# pcm2704_CMoy.net
KiCad netlist of a schematic drawn in EAGLE
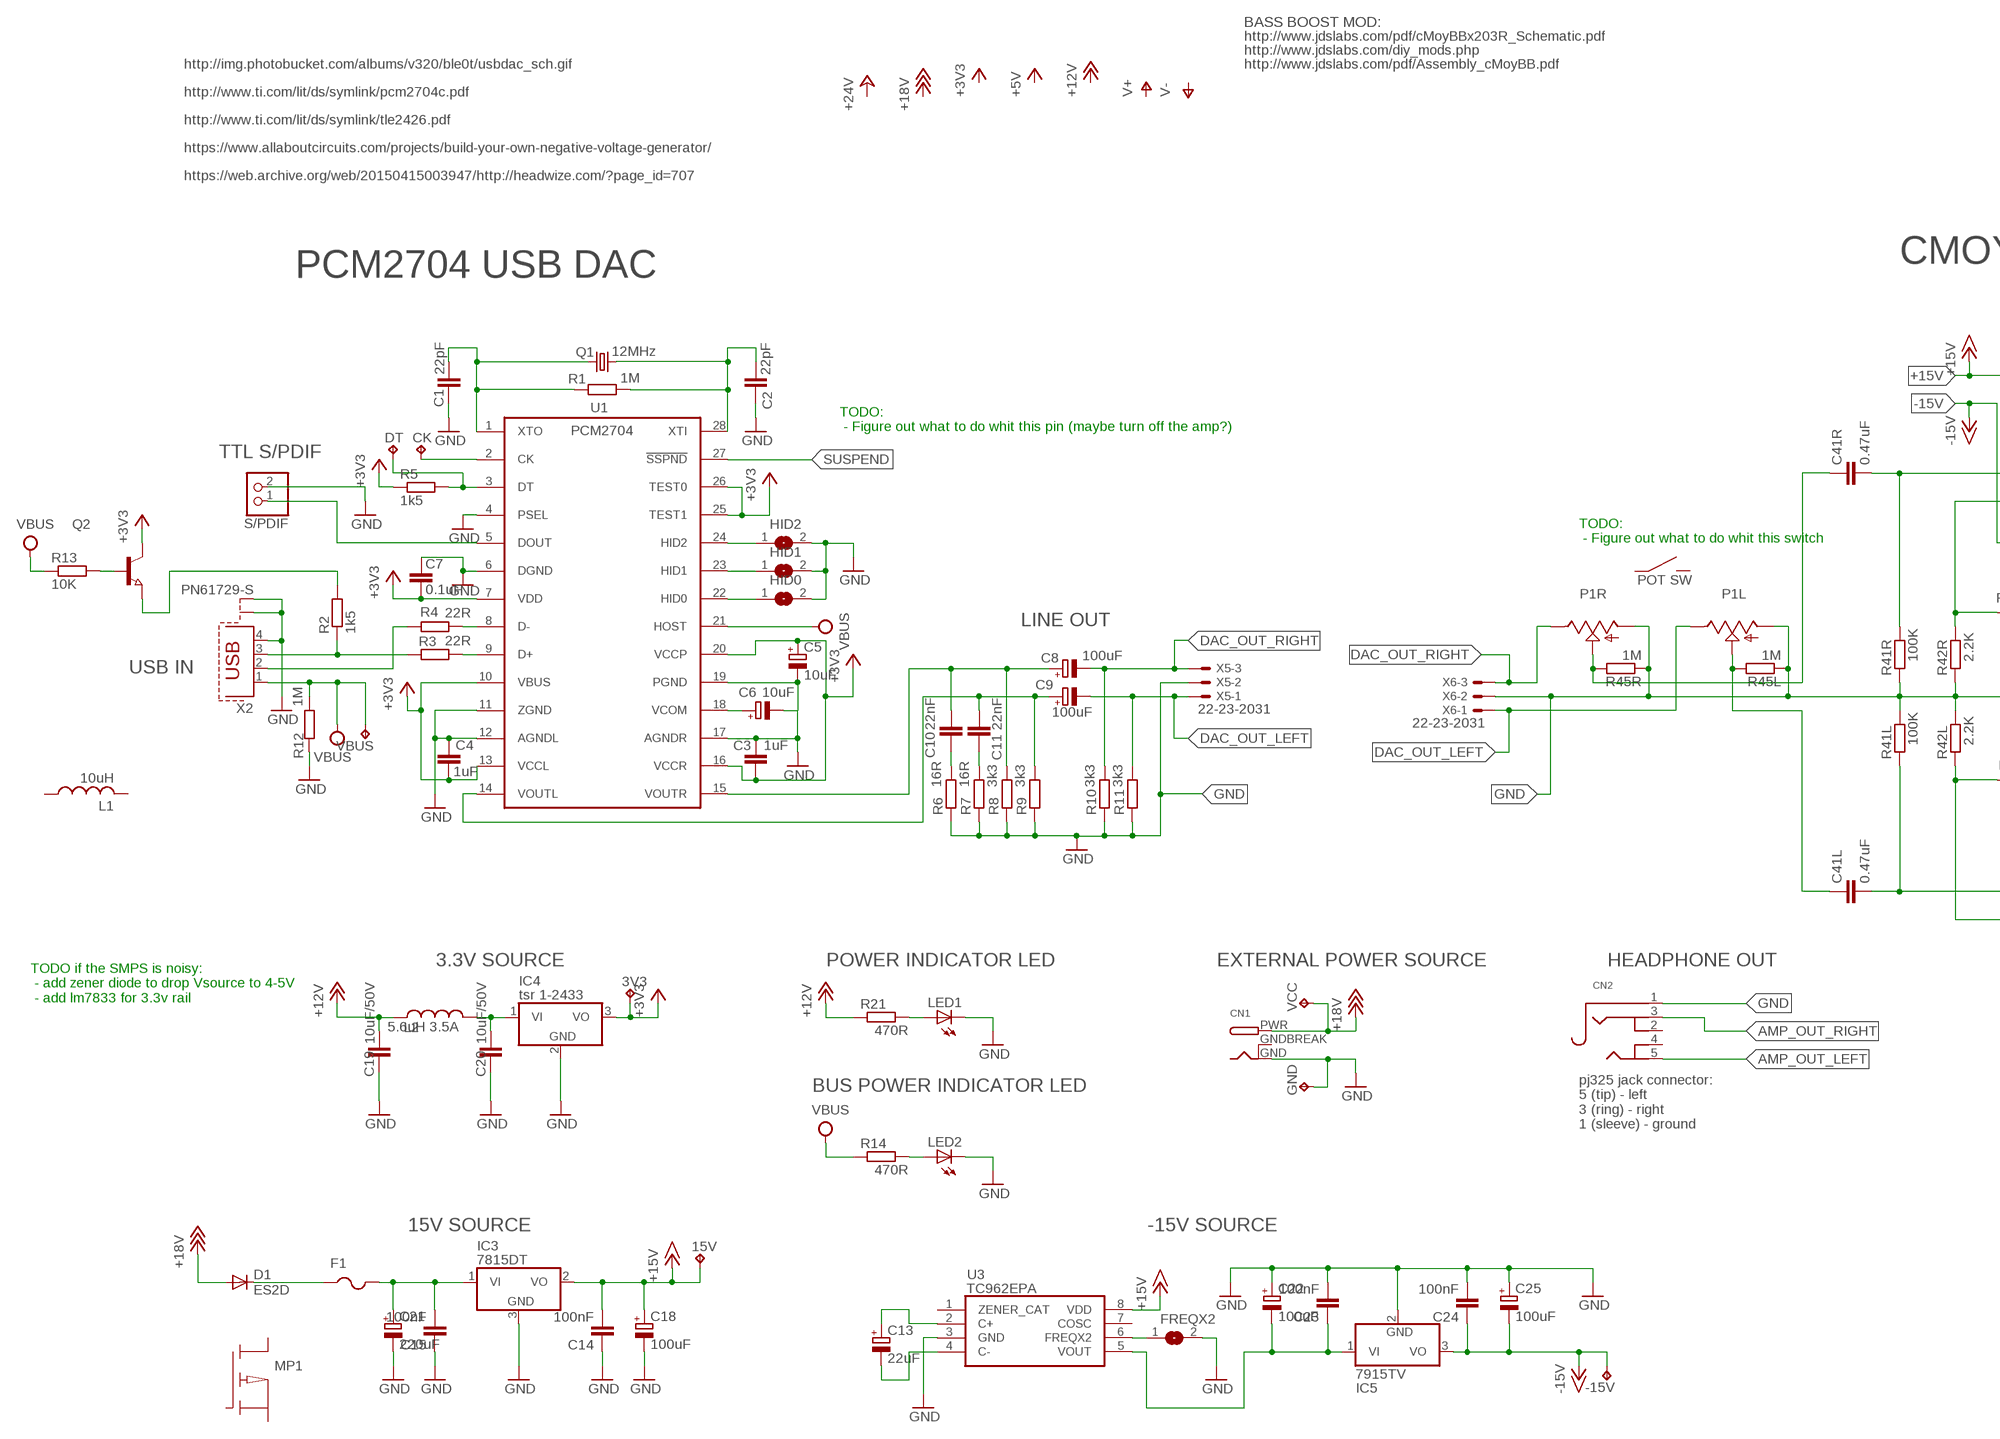
[diagram p0: schematic, sheet 1, part 1 of 2]
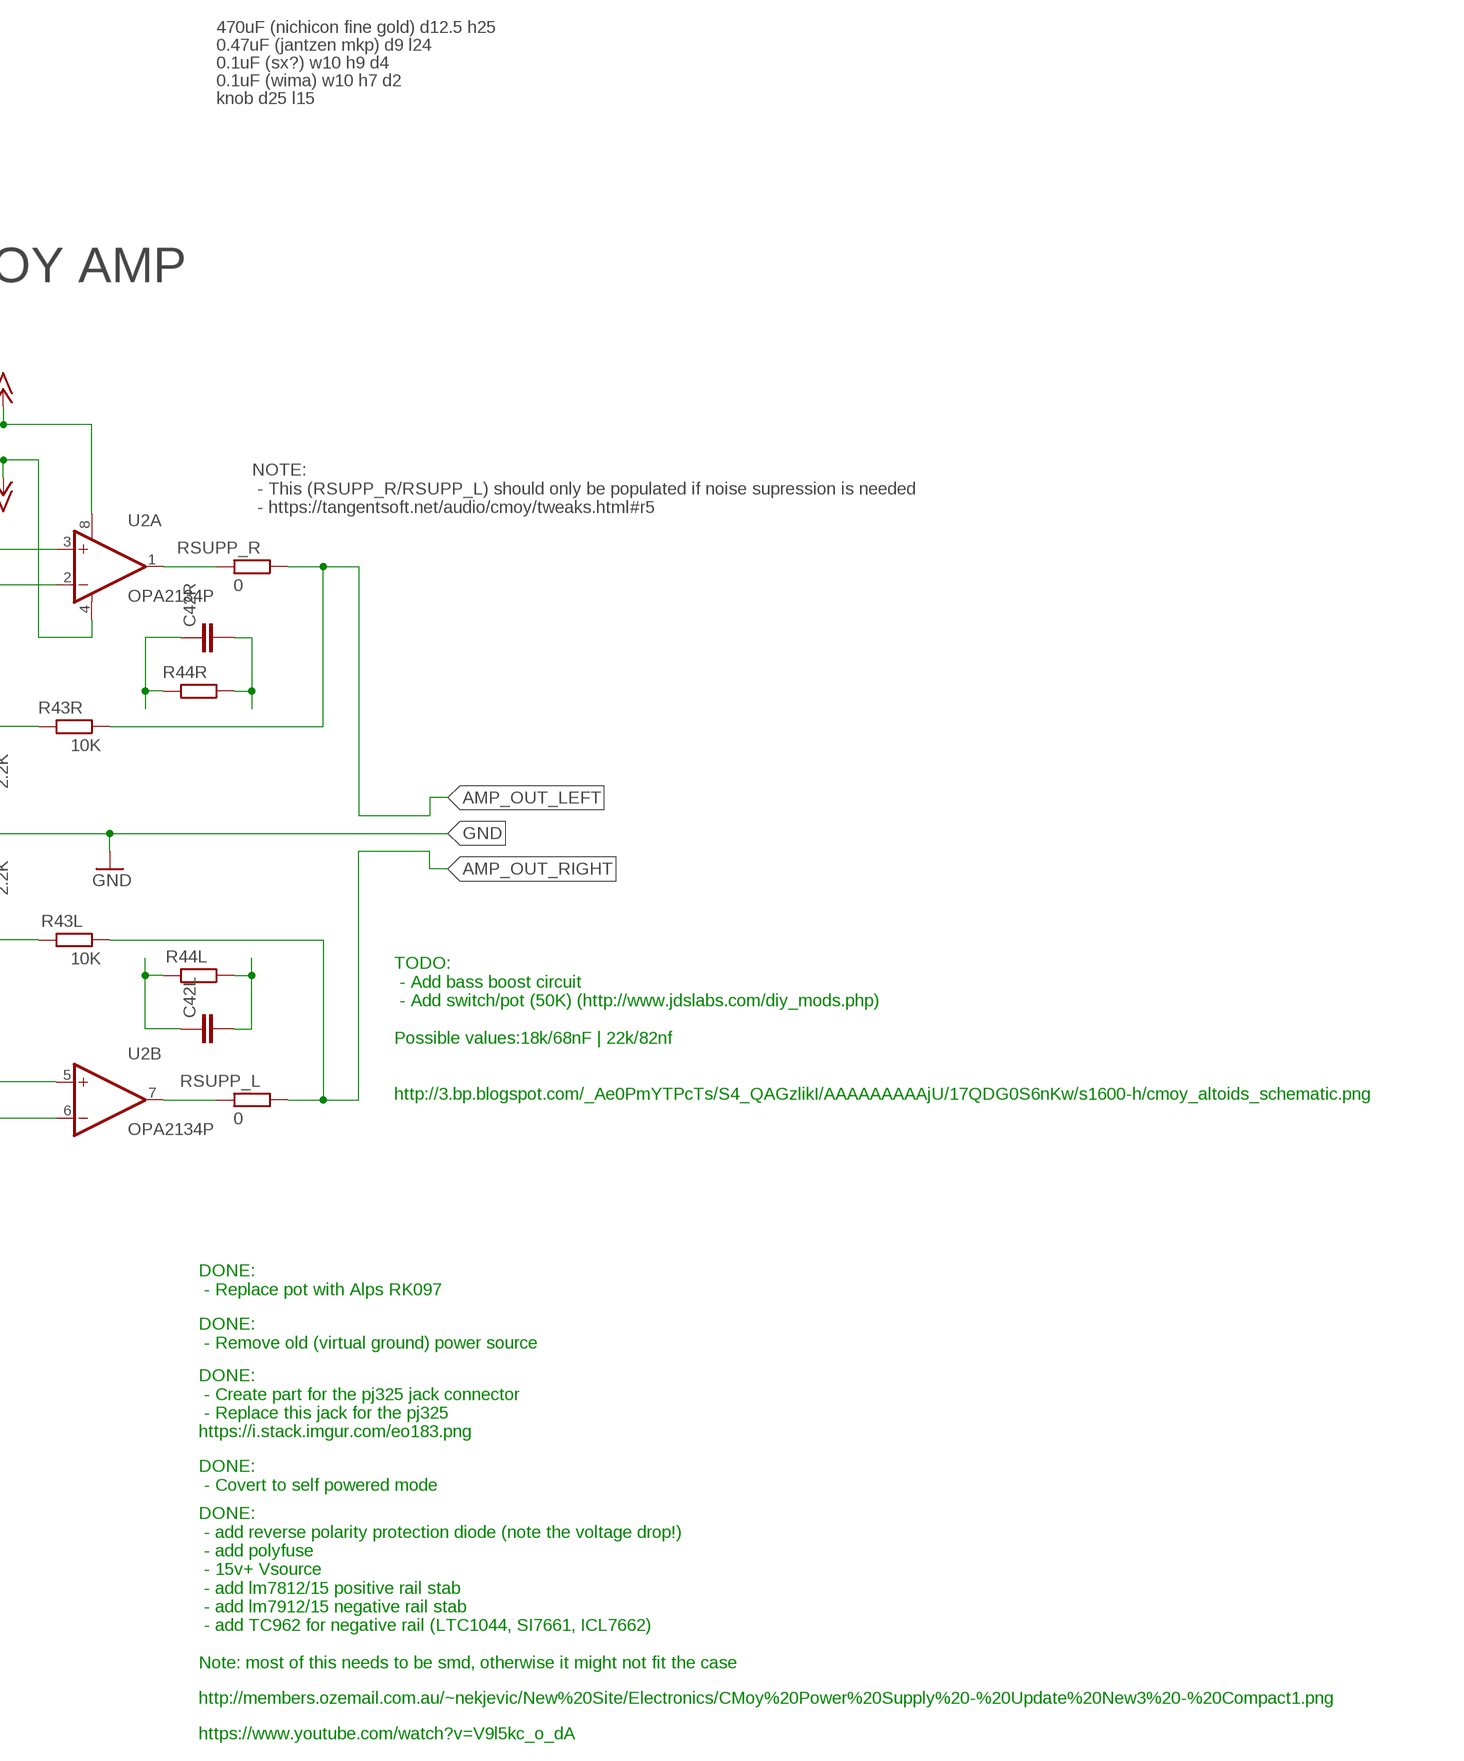
[diagram p1: schematic, sheet 1, part 2 of 2]

(export (version "E")
  (design (tool "Eeschema 10.0.6"))
  (components
    (comp (ref "-15V")
      (value "TPTP20R")
      (footprint "eagle-import:TP20R")
      (libsource (lib "eagle-import") (part "TPTP20R"))
    )
    (comp (ref "3V3")
      (value "TPTP20R")
      (footprint "eagle-import:TP20R")
      (libsource (lib "eagle-import") (part "TPTP20R"))
    )
    (comp (ref "15V")
      (value "TPTP20R")
      (footprint "eagle-import:TP20R")
      (libsource (lib "eagle-import") (part "TPTP20R"))
    )
    (comp (ref "C1")
      (value "22pF")
      (footprint "eagle-import:C0805")
      (libsource (lib "eagle-import") (part "C-EUC0805"))
    )
    (comp (ref "C2")
      (value "22pF")
      (footprint "eagle-import:C0805")
      (libsource (lib "eagle-import") (part "C-EUC0805"))
    )
    (comp (ref "C3")
      (value "1uF")
      (footprint "eagle-import:C0805")
      (libsource (lib "eagle-import") (part "C-EUC0805"))
    )
    (comp (ref "C4")
      (value "1uF")
      (footprint "eagle-import:C0805")
      (libsource (lib "eagle-import") (part "C-EUC0805"))
    )
    (comp (ref "C5")
      (value "10uF")
      (footprint "eagle-import:E2,5-7")
      (libsource (lib "eagle-import") (part "CPOL-EUE2.5-7"))
    )
    (comp (ref "C6")
      (value "10uF")
      (footprint "eagle-import:E2,5-7")
      (libsource (lib "eagle-import") (part "rcl_CPOL-EUE2.5-7"))
    )
    (comp (ref "C7")
      (value "0.1uF")
      (footprint "eagle-import:C0805")
      (libsource (lib "eagle-import") (part "C-EUC0805"))
    )
    (comp (ref "C8")
      (value "100uF")
      (footprint "eagle-import:E3,5-10")
      (libsource (lib "eagle-import") (part "rcl_CPOL-EUE3.5-10"))
    )
    (comp (ref "C9")
      (value "100uF")
      (footprint "eagle-import:E3,5-10")
      (libsource (lib "eagle-import") (part "rcl_CPOL-EUE3.5-10"))
    )
    (comp (ref "C10")
      (value "22nF")
      (footprint "eagle-import:C050-025X075")
      (libsource (lib "eagle-import") (part "C-EU050-025X075"))
    )
    (comp (ref "C11")
      (value "22nF")
      (footprint "eagle-import:C050-025X075")
      (libsource (lib "eagle-import") (part "C-EU050-025X075"))
    )
    (comp (ref "C13")
      (value "22uF")
      (footprint "eagle-import:E2,5-7")
      (libsource (lib "eagle-import") (part "rcl_CPOL-EUE2.5-7"))
    )
    (comp (ref "C14")
      (value "100nF")
      (footprint "eagle-import:C1206")
      (libsource (lib "eagle-import") (part "C-EUC1206"))
    )
    (comp (ref "C15")
      (value "100nF")
      (footprint "eagle-import:C1206")
      (libsource (lib "eagle-import") (part "C-EUC1206"))
    )
    (comp (ref "C18")
      (value "100uF")
      (footprint "eagle-import:E2,5-7")
      (libsource (lib "eagle-import") (part "rcl_CPOL-EUE2.5-7"))
    )
    (comp (ref "C19")
      (value "10uF/50V")
      (footprint "eagle-import:C1206")
      (libsource (lib "eagle-import") (part "C-EUC1206"))
    )
    (comp (ref "C20")
      (value "10uF/50V")
      (footprint "eagle-import:C1206")
      (libsource (lib "eagle-import") (part "C-EUC1206"))
    )
    (comp (ref "C21")
      (value "220uF")
      (footprint "eagle-import:E2,5-7")
      (libsource (lib "eagle-import") (part "rcl_CPOL-EUE2.5-7"))
    )
    (comp (ref "C22")
      (value "100uF")
      (footprint "eagle-import:E2,5-7")
      (libsource (lib "eagle-import") (part "rcl_CPOL-EUE2.5-7"))
    )
    (comp (ref "C23")
      (value "100nF")
      (footprint "eagle-import:C1206")
      (libsource (lib "eagle-import") (part "C-EUC1206"))
    )
    (comp (ref "C24")
      (value "100nF")
      (footprint "eagle-import:C1206")
      (libsource (lib "eagle-import") (part "C-EUC1206"))
    )
    (comp (ref "C25")
      (value "100uF")
      (footprint "eagle-import:E2,5-7")
      (libsource (lib "eagle-import") (part "rcl_CPOL-EUE2.5-7"))
    )
    (comp (ref "C41L")
      (value "0.47uF")
      (footprint "eagle-import:C27.5B11")
      (libsource (lib "eagle-import") (part "C27/11"))
    )
    (comp (ref "C41R")
      (value "0.47uF")
      (footprint "eagle-import:C27.5B11")
      (libsource (lib "eagle-import") (part "C27/11"))
    )
    (comp (ref "C42L")
      (value "C7.5/4")
      (footprint "eagle-import:C7.5B4")
      (libsource (lib "eagle-import") (part "C7.5/4"))
    )
    (comp (ref "C42R")
      (value "C7.5/4")
      (footprint "eagle-import:C7.5B4")
      (libsource (lib "eagle-import") (part "C7.5/4"))
    )
    (comp (ref "CK")
      (value "TPTP20R")
      (footprint "eagle-import:TP20R")
      (libsource (lib "eagle-import") (part "TPTP20R"))
    )
    (comp (ref "CN1")
      (value "DCBARRELPTH")
      (footprint "eagle-import:DCJACK_2MM_PTH")
      (libsource (lib "eagle-import") (part "DCBARRELPTH"))
    )
    (comp (ref "CN2")
      (value "AUDIO_3.5MMJACKPTH")
      (footprint "eagle-import:4UCONN_05550")
      (libsource (lib "eagle-import") (part "AUDIO_3.5MMJACKPTH"))
    )
    (comp (ref "D1")
      (value "ES2D")
      (footprint "eagle-import:SMB")
      (libsource (lib "eagle-import") (part "ES2D"))
    )
    (comp (ref "DT")
      (value "TPTP20R")
      (footprint "eagle-import:TP20R")
      (libsource (lib "eagle-import") (part "TPTP20R"))
    )
    (comp (ref "F1")
      (value "PTCFUSE-1812")
      (footprint "eagle-import:1812")
      (libsource (lib "eagle-import") (part "PTCFUSE-1812"))
    )
    (comp (ref "FREQX2")
      (value "SJ")
      (footprint "eagle-import:SJ")
      (libsource (lib "eagle-import") (part "SJ"))
    )
    (comp (ref "GND")
      (value "TPTP20R")
      (footprint "eagle-import:TP20R")
      (libsource (lib "eagle-import") (part "TPTP20R"))
    )
    (comp (ref "HID0")
      (value "SJ")
      (footprint "eagle-import:SJ")
      (libsource (lib "eagle-import") (part "SJ"))
    )
    (comp (ref "HID1")
      (value "SJ")
      (footprint "eagle-import:SJ")
      (libsource (lib "eagle-import") (part "SJ"))
    )
    (comp (ref "HID2")
      (value "SJ")
      (footprint "eagle-import:SJ")
      (libsource (lib "eagle-import") (part "SJ"))
    )
    (comp (ref "IC3")
      (value "7815DT")
      (footprint "eagle-import:TO252")
      (libsource (lib "eagle-import") (part "78DT15"))
    )
    (comp (ref "IC4")
      (value "tsr 1-2433")
      (footprint "eagle-import:TO220V")
      (libsource (lib "eagle-import") (part "78TV05"))
    )
    (comp (ref "IC5")
      (value "7915TV")
      (footprint "eagle-import:TO220V")
      (libsource (lib "eagle-import") (part "78TV15"))
    )
    (comp (ref "L1")
      (value "10uH")
      (footprint "eagle-import:L1812")
      (libsource (lib "eagle-import") (part "L-USL1812"))
    )
    (comp (ref "L2")
      (value "5.6uH 3.5A")
      (footprint "eagle-import:L1812")
      (libsource (lib "eagle-import") (part "L-USL1812"))
    )
    (comp (ref "LED1")
      (value "LED3MM")
      (footprint "eagle-import:LED3MM")
      (libsource (lib "eagle-import") (part "LED3MM"))
    )
    (comp (ref "LED2")
      (value "LED3MM")
      (footprint "eagle-import:LED3MM")
      (libsource (lib "eagle-import") (part "LED3MM"))
    )
    (comp (ref "MP1")
      (value "PMOS")
      (footprint "eagle-import:SOT23")
      (libsource (lib "eagle-import") (part "PMOS"))
    )
    (comp (ref "P1")
      (value "ALPS_RK0971221Z0N")
      (footprint "eagle-import:ALPS_RK0971221Z0X")
      (libsource (lib "eagle-import") (part "ALPS_RK0971221Z0N"))
    )
    (comp (ref "Q1")
      (value "12MHz")
      (footprint "eagle-import:HC49_S")
      (libsource (lib "eagle-import") (part "CRYSTALHC49S"))
    )
    (comp (ref "Q2")
      (value "NPN-TRANSISTOR_SOT23")
      (footprint "eagle-import:SOT23")
      (libsource (lib "eagle-import") (part "NPN-TRANSISTOR_SOT23"))
    )
    (comp (ref "R1")
      (value "1M")
      (footprint "eagle-import:M0805")
      (libsource (lib "eagle-import") (part "R-EU_M0805"))
    )
    (comp (ref "R2")
      (value "1k5")
      (footprint "eagle-import:R0805")
      (libsource (lib "eagle-import") (part "R-EU_R0805"))
    )
    (comp (ref "R3")
      (value "22R")
      (footprint "eagle-import:R0805")
      (libsource (lib "eagle-import") (part "R-EU_R0805"))
    )
    (comp (ref "R4")
      (value "22R")
      (footprint "eagle-import:R0805")
      (libsource (lib "eagle-import") (part "R-EU_R0805"))
    )
    (comp (ref "R5")
      (value "1k5")
      (footprint "eagle-import:R0805")
      (libsource (lib "eagle-import") (part "R-EU_R0805"))
    )
    (comp (ref "R6")
      (value "16R")
      (footprint "eagle-import:0204_7")
      (libsource (lib "eagle-import") (part "R-EU_0204/7"))
    )
    (comp (ref "R7")
      (value "16R")
      (footprint "eagle-import:0204_7")
      (libsource (lib "eagle-import") (part "R-EU_0204/7"))
    )
    (comp (ref "R8")
      (value "3k3")
      (footprint "eagle-import:0204_7")
      (libsource (lib "eagle-import") (part "R-EU_0204/7"))
    )
    (comp (ref "R9")
      (value "3k3")
      (footprint "eagle-import:0204_7")
      (libsource (lib "eagle-import") (part "R-EU_0204/7"))
    )
    (comp (ref "R10")
      (value "3k3")
      (footprint "eagle-import:0204_7")
      (libsource (lib "eagle-import") (part "R-EU_0204/7"))
    )
    (comp (ref "R11")
      (value "3k3")
      (footprint "eagle-import:0204_7")
      (libsource (lib "eagle-import") (part "R-EU_0204/7"))
    )
    (comp (ref "R12")
      (value "1M")
      (footprint "eagle-import:M0805")
      (libsource (lib "eagle-import") (part "R-EU_M0805"))
    )
    (comp (ref "R13")
      (value "10K")
      (footprint "eagle-import:R0805")
      (libsource (lib "eagle-import") (part "R-EU_R0805"))
    )
    (comp (ref "R14")
      (value "470R")
      (footprint "eagle-import:0204_7")
      (libsource (lib "eagle-import") (part "R-EU_0204/7"))
    )
    (comp (ref "R21")
      (value "470R")
      (footprint "eagle-import:0204_7")
      (libsource (lib "eagle-import") (part "R-EU_0204/7"))
    )
    (comp (ref "R41L")
      (value "100K")
      (footprint "eagle-import:0204_7")
      (libsource (lib "eagle-import") (part "R-EU_0204/7"))
    )
    (comp (ref "R41R")
      (value "100K")
      (footprint "eagle-import:0204_7")
      (libsource (lib "eagle-import") (part "R-EU_0204/7"))
    )
    (comp (ref "R42L")
      (value "2.2K")
      (footprint "eagle-import:0204_7")
      (libsource (lib "eagle-import") (part "R-EU_0204/7"))
    )
    (comp (ref "R42R")
      (value "2.2K")
      (footprint "eagle-import:0204_7")
      (libsource (lib "eagle-import") (part "R-EU_0204/7"))
    )
    (comp (ref "R43L")
      (value "10K")
      (footprint "eagle-import:0204_7")
      (libsource (lib "eagle-import") (part "R-EU_0204/7"))
    )
    (comp (ref "R43R")
      (value "10K")
      (footprint "eagle-import:0204_7")
      (libsource (lib "eagle-import") (part "R-EU_0204/7"))
    )
    (comp (ref "R44L")
      (value "R-EU_0204/7")
      (footprint "eagle-import:0204_7")
      (libsource (lib "eagle-import") (part "R-EU_0204/7"))
    )
    (comp (ref "R44R")
      (value "R-EU_0204/7")
      (footprint "eagle-import:0204_7")
      (libsource (lib "eagle-import") (part "R-EU_0204/7"))
    )
    (comp (ref "R45L")
      (value "1M")
      (footprint "eagle-import:0204_7")
      (libsource (lib "eagle-import") (part "R-EU_0204/7"))
    )
    (comp (ref "R45R")
      (value "1M")
      (footprint "eagle-import:0204_7")
      (libsource (lib "eagle-import") (part "R-EU_0204/7"))
    )
    (comp (ref "RSUPP_L")
      (value "0")
      (footprint "eagle-import:0204_7")
      (libsource (lib "eagle-import") (part "R-EU_0204/7"))
    )
    (comp (ref "RSUPP_R")
      (value "0")
      (footprint "eagle-import:0204_7")
      (libsource (lib "eagle-import") (part "R-EU_0204/7"))
    )
    (comp (ref "S/PDIF")
      (value "PINHD-1X2")
      (footprint "eagle-import:1X02")
      (libsource (lib "eagle-import") (part "PINHD-1X2"))
    )
    (comp (ref "U1")
      (value "PCM2704")
      (footprint "eagle-import:SSOP28DB")
      (libsource (lib "eagle-import") (part "PCM2704"))
    )
    (comp (ref "U2")
      (value "OPA2134P")
      (footprint "eagle-import:DIL08")
      (fields (field (name "MF") "TEXAS INSTRUMENTS") (field (name "MPN") "OPA2134PA"))
      (libsource (lib "eagle-import") (part "OPA2134P"))
    )
    (comp (ref "U3")
      (value "TC962EPA")
      (footprint "eagle-import:PDIP8_300MC")
      (libsource (lib "eagle-import") (part "TC962EPA"))
    )
    (comp (ref "VBUS")
      (value "TPTP20R")
      (footprint "eagle-import:TP20R")
      (libsource (lib "eagle-import") (part "TPTP20R"))
    )
    (comp (ref "VCC")
      (value "TPTP20R")
      (footprint "eagle-import:TP20R")
      (libsource (lib "eagle-import") (part "TPTP20R"))
    )
    (comp (ref "X2")
      (value "PN61729-S")
      (footprint "eagle-import:PN61729-S")
      (libsource (lib "eagle-import") (part "PN61729-S"))
    )
    (comp (ref "X5")
      (value "22-23-2031")
      (footprint "eagle-import:22-23-2031")
      (fields (field (name "MF") "MOLEX"))
      (libsource (lib "eagle-import") (part "22-23-2031"))
    )
    (comp (ref "X6")
      (value "22-23-2031")
      (footprint "eagle-import:22-23-2031")
      (fields (field (name "MF") "MOLEX"))
      (libsource (lib "eagle-import") (part "22-23-2031"))
    )
  )
  (nets
    (net (code "1") (name "+3V3") (class "Default")
      (node (ref "3V3") (pin "TP") (pinfunction "TP_TP") (pintype "input"))
      (node (ref "C3") (pin "1") (pinfunction "1_1") (pintype "passive"))
      (node (ref "C4") (pin "2") (pinfunction "2_2") (pintype "passive"))
      (node (ref "C5") (pin "+") (pinfunction "+_+") (pintype "passive"))
      (node (ref "C7") (pin "2") (pinfunction "2_2") (pintype "passive"))
      (node (ref "IC4") (pin "3") (pinfunction "VO_3") (pintype "passive"))
      (node (ref "Q2") (pin "3") (pinfunction "C_3") (pintype "passive"))
      (node (ref "R5") (pin "1") (pinfunction "1_1") (pintype "passive"))
      (node (ref "U1") (pin "10") (pinfunction "VBUS_10") (pintype "power_in"))
      (node (ref "U1") (pin "13") (pinfunction "VCCL_13") (pintype "power_in"))
      (node (ref "U1") (pin "16") (pinfunction "VCCR_16") (pintype "power_in"))
      (node (ref "U1") (pin "20") (pinfunction "VCCP_20") (pintype "power_in"))
      (node (ref "U1") (pin "25") (pinfunction "TEST1_25") (pintype "input"))
      (node (ref "U1") (pin "26") (pinfunction "TEST0_26") (pintype "input"))
      (node (ref "U1") (pin "7") (pinfunction "VDD_7") (pintype "power_in"))
    )
    (net (code "3") (name "+12V") (class "Default")
      (node (ref "C19") (pin "2") (pinfunction "2_2") (pintype "passive"))
      (node (ref "L2") (pin "1") (pinfunction "1_1") (pintype "passive"))
      (node (ref "R21") (pin "1") (pinfunction "1_1") (pintype "passive"))
    )
    (net (code "4") (name "+15V") (class "Default")
      (node (ref "15V") (pin "TP") (pinfunction "TP_TP") (pintype "input"))
      (node (ref "C14") (pin "2") (pinfunction "2_2") (pintype "passive"))
      (node (ref "C18") (pin "+") (pinfunction "+_+") (pintype "passive"))
      (node (ref "IC3") (pin "2") (pinfunction "VO_2") (pintype "passive"))
      (node (ref "U2") (pin "8") (pinfunction "V+_8") (pintype "power_in"))
      (node (ref "U3") (pin "8") (pinfunction "VDD_8") (pintype "passive"))
    )
    (net (code "5") (name "+18V") (class "Default")
      (node (ref "CN1") (pin "PWR") (pinfunction "PWR_PWR") (pintype "power_in"))
      (node (ref "D1") (pin "A") (pinfunction "A_A") (pintype "passive"))
      (node (ref "VCC") (pin "TP") (pinfunction "TP_TP") (pintype "input"))
    )
    (net (code "7") (name "-15V") (class "Default")
      (node (ref "-15V") (pin "TP") (pinfunction "TP_TP") (pintype "input"))
      (node (ref "C24") (pin "1") (pinfunction "1_1") (pintype "passive"))
      (node (ref "C25") (pin "-") (pinfunction "-_-") (pintype "passive"))
      (node (ref "IC5") (pin "3") (pinfunction "VO_3") (pintype "passive"))
      (node (ref "U2") (pin "4") (pinfunction "V-_4") (pintype "power_in"))
    )
    (net (code "8") (name "/GNDBREAK") (class "Default")
      (node (ref "CN1") (pin "GNDBREAK") (pinfunction "GNDBREAK_GNDBREAK") (pintype "power_in"))
    )
    (net (code "9") (name "/S1") (class "Default")
      (node (ref "P1") (pin "S1") (pinfunction "S1_S1") (pintype "power_in"))
    )
    (net (code "10") (name "/S2") (class "Default")
      (node (ref "P1") (pin "S2") (pinfunction "S2_S2") (pintype "power_in"))
    )
    (net (code "11") (name "AMP_OUT_LEFT") (class "Default")
      (node (ref "CN2") (pin "5") (pinfunction "P$5_5") (pintype "bidirectional"))
      (node (ref "R43R") (pin "1") (pinfunction "1_1") (pintype "passive"))
      (node (ref "RSUPP_R") (pin "1") (pinfunction "1_1") (pintype "passive"))
    )
    (net (code "12") (name "AMP_OUT_RIGHT") (class "Default")
      (node (ref "CN2") (pin "3") (pinfunction "P$2_3") (pintype "bidirectional"))
      (node (ref "R43L") (pin "1") (pinfunction "1_1") (pintype "passive"))
      (node (ref "RSUPP_L") (pin "1") (pinfunction "1_1") (pintype "passive"))
    )
    (net (code "13") (name "DAC_OUT_LEFT") (class "Default")
      (node (ref "C9") (pin "-") (pinfunction "-_-") (pintype "passive"))
      (node (ref "P1") (pin "I1") (pinfunction "3_I1") (pintype "passive"))
      (node (ref "R11") (pin "2") (pinfunction "2_2") (pintype "passive"))
      (node (ref "X5") (pin "1") (pinfunction "S_1") (pintype "passive"))
      (node (ref "X6") (pin "1") (pinfunction "S_1") (pintype "passive"))
    )
    (net (code "14") (name "DAC_OUT_RIGHT") (class "Default")
      (node (ref "C8") (pin "-") (pinfunction "-_-") (pintype "passive"))
      (node (ref "P1") (pin "I2") (pinfunction "3_I2") (pintype "passive"))
      (node (ref "R10") (pin "2") (pinfunction "2_2") (pintype "passive"))
      (node (ref "X5") (pin "3") (pinfunction "S_3") (pintype "passive"))
      (node (ref "X6") (pin "3") (pinfunction "S_3") (pintype "passive"))
    )
    (net (code "15") (name "GND") (class "Default")
      (node (ref "C1") (pin "2") (pinfunction "2_2") (pintype "passive"))
      (node (ref "C14") (pin "1") (pinfunction "1_1") (pintype "passive"))
      (node (ref "C15") (pin "1") (pinfunction "1_1") (pintype "passive"))
      (node (ref "C18") (pin "-") (pinfunction "-_-") (pintype "passive"))
      (node (ref "C19") (pin "1") (pinfunction "1_1") (pintype "passive"))
      (node (ref "C2") (pin "2") (pinfunction "2_2") (pintype "passive"))
      (node (ref "C20") (pin "1") (pinfunction "1_1") (pintype "passive"))
      (node (ref "C21") (pin "-") (pinfunction "-_-") (pintype "passive"))
      (node (ref "C22") (pin "+") (pinfunction "+_+") (pintype "passive"))
      (node (ref "C23") (pin "2") (pinfunction "2_2") (pintype "passive"))
      (node (ref "C24") (pin "2") (pinfunction "2_2") (pintype "passive"))
      (node (ref "C25") (pin "+") (pinfunction "+_+") (pintype "passive"))
      (node (ref "C3") (pin "2") (pinfunction "2_2") (pintype "passive"))
      (node (ref "C4") (pin "1") (pinfunction "1_1") (pintype "passive"))
      (node (ref "C5") (pin "-") (pinfunction "-_-") (pintype "passive"))
      (node (ref "C6") (pin "-") (pinfunction "-_-") (pintype "passive"))
      (node (ref "C7") (pin "1") (pinfunction "1_1") (pintype "passive"))
      (node (ref "CN1") (pin "GND") (pinfunction "GND_GND") (pintype "power_in"))
      (node (ref "CN2") (pin "1") (pinfunction "P$1_1") (pintype "bidirectional"))
      (node (ref "FREQX2") (pin "2") (pinfunction "2_2") (pintype "passive"))
      (node (ref "GND") (pin "TP") (pinfunction "TP_TP") (pintype "input"))
      (node (ref "HID0") (pin "2") (pinfunction "2_2") (pintype "passive"))
      (node (ref "HID1") (pin "2") (pinfunction "2_2") (pintype "passive"))
      (node (ref "HID2") (pin "2") (pinfunction "2_2") (pintype "passive"))
      (node (ref "IC3") (pin "3") (pinfunction "GND_3") (pintype "passive"))
      (node (ref "IC4") (pin "2") (pinfunction "GND_2") (pintype "passive"))
      (node (ref "IC5") (pin "2") (pinfunction "GND_2") (pintype "passive"))
      (node (ref "LED1") (pin "K") (pinfunction "C_K") (pintype "passive"))
      (node (ref "LED2") (pin "K") (pinfunction "C_K") (pintype "passive"))
      (node (ref "P1") (pin "G1") (pinfunction "1_G1") (pintype "passive"))
      (node (ref "P1") (pin "G2") (pinfunction "1_G2") (pintype "passive"))
      (node (ref "R10") (pin "1") (pinfunction "1_1") (pintype "passive"))
      (node (ref "R11") (pin "1") (pinfunction "1_1") (pintype "passive"))
      (node (ref "R12") (pin "1") (pinfunction "1_1") (pintype "passive"))
      (node (ref "R41L") (pin "2") (pinfunction "2_2") (pintype "passive"))
      (node (ref "R41R") (pin "1") (pinfunction "1_1") (pintype "passive"))
      (node (ref "R42L") (pin "2") (pinfunction "2_2") (pintype "passive"))
      (node (ref "R42R") (pin "1") (pinfunction "1_1") (pintype "passive"))
      (node (ref "R45L") (pin "1") (pinfunction "1_1") (pintype "passive"))
      (node (ref "R45R") (pin "1") (pinfunction "1_1") (pintype "passive"))
      (node (ref "R6") (pin "1") (pinfunction "1_1") (pintype "passive"))
      (node (ref "R7") (pin "1") (pinfunction "1_1") (pintype "passive"))
      (node (ref "R8") (pin "1") (pinfunction "1_1") (pintype "passive"))
      (node (ref "R9") (pin "1") (pinfunction "1_1") (pintype "passive"))
      (node (ref "S/PDIF") (pin "2") (pinfunction "2_2") (pintype "passive"))
      (node (ref "U1") (pin "11") (pinfunction "ZGND_11") (pintype "power_in"))
      (node (ref "U1") (pin "12") (pinfunction "AGNDL_12") (pintype "power_in"))
      (node (ref "U1") (pin "17") (pinfunction "AGNDR_17") (pintype "power_in"))
      (node (ref "U1") (pin "19") (pinfunction "PGND_19") (pintype "power_in"))
      (node (ref "U1") (pin "4") (pinfunction "PSEL_4") (pintype "input"))
      (node (ref "U1") (pin "6") (pinfunction "DGND_6") (pintype "power_in"))
      (node (ref "U3") (pin "3") (pinfunction "GND_3") (pintype "passive"))
      (node (ref "X2") (pin "4") (pinfunction "4_4") (pintype "passive"))
      (node (ref "X2") (pin "S1") (pinfunction "S1_S1") (pintype "passive"))
      (node (ref "X2") (pin "S2") (pinfunction "S2_S2") (pintype "passive"))
      (node (ref "X5") (pin "2") (pinfunction "S_2") (pintype "passive"))
      (node (ref "X6") (pin "2") (pinfunction "S_2") (pintype "passive"))
    )
    (net (code "16") (name "Net-(C10-Pad2)") (class "Default")
      (node (ref "C10") (pin "2") (pinfunction "2_2") (pintype "passive"))
      (node (ref "R6") (pin "2") (pinfunction "2_2") (pintype "passive"))
    )
    (net (code "17") (name "Net-(C11-Pad2)") (class "Default")
      (node (ref "C11") (pin "2") (pinfunction "2_2") (pintype "passive"))
      (node (ref "R7") (pin "2") (pinfunction "2_2") (pintype "passive"))
    )
    (net (code "18") (name "Net-(C42L-Pad1)") (class "Default")
      (node (ref "C42L") (pin "1") (pinfunction "1_1") (pintype "passive"))
      (node (ref "R44L") (pin "2") (pinfunction "2_2") (pintype "passive"))
    )
    (net (code "19") (name "Net-(C42L-Pad2)") (class "Default")
      (node (ref "C42L") (pin "2") (pinfunction "2_2") (pintype "passive"))
      (node (ref "R44L") (pin "1") (pinfunction "1_1") (pintype "passive"))
    )
    (net (code "20") (name "Net-(C42R-Pad1)") (class "Default")
      (node (ref "C42R") (pin "1") (pinfunction "1_1") (pintype "passive"))
      (node (ref "R44R") (pin "2") (pinfunction "2_2") (pintype "passive"))
    )
    (net (code "21") (name "Net-(C42R-Pad2)") (class "Default")
      (node (ref "C42R") (pin "2") (pinfunction "2_2") (pintype "passive"))
      (node (ref "R44R") (pin "1") (pinfunction "1_1") (pintype "passive"))
    )
    (net (code "22") (name "Net-(D1-PadC)") (class "Default")
      (node (ref "D1") (pin "C") (pinfunction "C_C") (pintype "passive"))
      (node (ref "F1") (pin "1") (pinfunction "1_1") (pintype "passive"))
    )
    (net (code "23") (name "Net-(IC3-VI)") (class "Default")
      (node (ref "C15") (pin "2") (pinfunction "2_2") (pintype "passive"))
      (node (ref "C21") (pin "+") (pinfunction "+_+") (pintype "passive"))
      (node (ref "F1") (pin "2") (pinfunction "2_2") (pintype "passive"))
      (node (ref "IC3") (pin "1") (pinfunction "VI_1") (pintype "input"))
    )
    (net (code "24") (name "Net-(IC4-VI)") (class "Default")
      (node (ref "C20") (pin "2") (pinfunction "2_2") (pintype "passive"))
      (node (ref "IC4") (pin "1") (pinfunction "VI_1") (pintype "input"))
      (node (ref "L2") (pin "2") (pinfunction "2_2") (pintype "passive"))
    )
    (net (code "25") (name "Net-(IC5-VI)") (class "Default")
      (node (ref "C22") (pin "-") (pinfunction "-_-") (pintype "passive"))
      (node (ref "C23") (pin "1") (pinfunction "1_1") (pintype "passive"))
      (node (ref "IC5") (pin "1") (pinfunction "VI_1") (pintype "input"))
      (node (ref "U3") (pin "5") (pinfunction "VOUT_5") (pintype "passive"))
    )
    (net (code "26") (name "Net-(LED1-PadA)") (class "Default")
      (node (ref "LED1") (pin "A") (pinfunction "A_A") (pintype "passive"))
      (node (ref "R21") (pin "2") (pinfunction "2_2") (pintype "passive"))
    )
    (net (code "27") (name "Net-(LED2-PadA)") (class "Default")
      (node (ref "LED2") (pin "A") (pinfunction "A_A") (pintype "passive"))
      (node (ref "R14") (pin "2") (pinfunction "2_2") (pintype "passive"))
    )
    (net (code "28") (name "Net-(P1B-2)") (class "Default")
      (node (ref "C41L") (pin "1") (pinfunction "1_1") (pintype "passive"))
      (node (ref "P1") (pin "O1") (pinfunction "2_O1") (pintype "passive"))
      (node (ref "R45L") (pin "2") (pinfunction "2_2") (pintype "passive"))
    )
    (net (code "29") (name "Net-(P1C-2)") (class "Default")
      (node (ref "C41R") (pin "1") (pinfunction "1_1") (pintype "passive"))
      (node (ref "P1") (pin "O2") (pinfunction "2_O2") (pintype "passive"))
      (node (ref "R45R") (pin "2") (pinfunction "2_2") (pintype "passive"))
    )
    (net (code "30") (name "Net-(Q2-B)") (class "Default")
      (node (ref "Q2") (pin "1") (pinfunction "B_1") (pintype "passive"))
      (node (ref "R13") (pin "2") (pinfunction "2_2") (pintype "passive"))
    )
    (net (code "31") (name "Net-(Q2-E)") (class "Default")
      (node (ref "Q2") (pin "2") (pinfunction "E_2") (pintype "passive"))
      (node (ref "R2") (pin "2") (pinfunction "2_2") (pintype "passive"))
    )
    (net (code "32") (name "Net-(R2-Pad1)") (class "Default")
      (node (ref "R2") (pin "1") (pinfunction "1_1") (pintype "passive"))
      (node (ref "R3") (pin "1") (pinfunction "1_1") (pintype "passive"))
      (node (ref "X2") (pin "3") (pinfunction "3_3") (pintype "passive"))
    )
    (net (code "33") (name "Net-(R4-Pad1)") (class "Default")
      (node (ref "R4") (pin "1") (pinfunction "1_1") (pintype "passive"))
      (node (ref "X2") (pin "2") (pinfunction "2_2") (pintype "passive"))
    )
    (net (code "34") (name "Net-(U1-CK)") (class "Default")
      (node (ref "CK") (pin "TP") (pinfunction "TP_TP") (pintype "input"))
      (node (ref "U1") (pin "2") (pinfunction "CK_2") (pintype "output"))
    )
    (net (code "35") (name "Net-(U1-D+)") (class "Default")
      (node (ref "R3") (pin "2") (pinfunction "2_2") (pintype "passive"))
      (node (ref "U1") (pin "9") (pinfunction "D+_9") (pintype "bidirectional"))
    )
    (net (code "36") (name "Net-(U1-D-)") (class "Default")
      (node (ref "R4") (pin "2") (pinfunction "2_2") (pintype "passive"))
      (node (ref "U1") (pin "8") (pinfunction "D-_8") (pintype "bidirectional"))
    )
    (net (code "37") (name "Net-(U1-DOUT)") (class "Default")
      (node (ref "S/PDIF") (pin "1") (pinfunction "1_1") (pintype "passive"))
      (node (ref "U1") (pin "5") (pinfunction "DOUT_5") (pintype "output"))
    )
    (net (code "38") (name "Net-(U1-DT)") (class "Default")
      (node (ref "DT") (pin "TP") (pinfunction "TP_TP") (pintype "input"))
      (node (ref "R5") (pin "2") (pinfunction "2_2") (pintype "passive"))
      (node (ref "U1") (pin "3") (pinfunction "DT_3") (pintype "bidirectional"))
    )
    (net (code "39") (name "Net-(U1-HID0)") (class "Default")
      (node (ref "HID0") (pin "1") (pinfunction "1_1") (pintype "passive"))
      (node (ref "U1") (pin "22") (pinfunction "HID0_22") (pintype "input"))
    )
    (net (code "40") (name "Net-(U1-HID1)") (class "Default")
      (node (ref "HID1") (pin "1") (pinfunction "1_1") (pintype "passive"))
      (node (ref "U1") (pin "23") (pinfunction "HID1_23") (pintype "input"))
    )
    (net (code "41") (name "Net-(U1-HID2)") (class "Default")
      (node (ref "HID2") (pin "1") (pinfunction "1_1") (pintype "passive"))
      (node (ref "U1") (pin "24") (pinfunction "HID2_24") (pintype "input"))
    )
    (net (code "42") (name "Net-(U1-VCOM)") (class "Default")
      (node (ref "C6") (pin "+") (pinfunction "+_+") (pintype "passive"))
      (node (ref "U1") (pin "18") (pinfunction "VCOM_18") (pintype "power_in"))
    )
    (net (code "43") (name "Net-(U1-VOUTL)") (class "Default")
      (node (ref "C11") (pin "1") (pinfunction "1_1") (pintype "passive"))
      (node (ref "C9") (pin "+") (pinfunction "+_+") (pintype "passive"))
      (node (ref "R9") (pin "2") (pinfunction "2_2") (pintype "passive"))
      (node (ref "U1") (pin "14") (pinfunction "VOUTL_14") (pintype "output"))
    )
    (net (code "44") (name "Net-(U1-VOUTR)") (class "Default")
      (node (ref "C10") (pin "1") (pinfunction "1_1") (pintype "passive"))
      (node (ref "C8") (pin "+") (pinfunction "+_+") (pintype "passive"))
      (node (ref "R8") (pin "2") (pinfunction "2_2") (pintype "passive"))
      (node (ref "U1") (pin "15") (pinfunction "VOUTR_15") (pintype "output"))
    )
    (net (code "45") (name "Net-(U1-XTI)") (class "Default")
      (node (ref "C2") (pin "1") (pinfunction "1_1") (pintype "passive"))
      (node (ref "Q1") (pin "2") (pinfunction "2_2") (pintype "passive"))
      (node (ref "R1") (pin "2") (pinfunction "2_2") (pintype "passive"))
      (node (ref "U1") (pin "28") (pinfunction "XTI_28") (pintype "input"))
    )
    (net (code "46") (name "Net-(U1-XTO)") (class "Default")
      (node (ref "C1") (pin "1") (pinfunction "1_1") (pintype "passive"))
      (node (ref "Q1") (pin "1") (pinfunction "1_1") (pintype "passive"))
      (node (ref "R1") (pin "1") (pinfunction "1_1") (pintype "passive"))
      (node (ref "U1") (pin "1") (pinfunction "XTO_1") (pintype "output"))
    )
    (net (code "47") (name "Net-(U2A-+IN)") (class "Default")
      (node (ref "C41R") (pin "2") (pinfunction "2_2") (pintype "passive"))
      (node (ref "R41R") (pin "2") (pinfunction "2_2") (pintype "passive"))
      (node (ref "U2") (pin "3") (pinfunction "+IN_3") (pintype "input"))
    )
    (net (code "48") (name "Net-(U2A--IN)") (class "Default")
      (node (ref "R42R") (pin "2") (pinfunction "2_2") (pintype "passive"))
      (node (ref "R43R") (pin "2") (pinfunction "2_2") (pintype "passive"))
      (node (ref "U2") (pin "2") (pinfunction "-IN_2") (pintype "input"))
    )
    (net (code "49") (name "Net-(U2A-OUT)") (class "Default")
      (node (ref "RSUPP_R") (pin "2") (pinfunction "2_2") (pintype "passive"))
      (node (ref "U2") (pin "1") (pinfunction "OUT_1") (pintype "output"))
    )
    (net (code "50") (name "Net-(U2B-+IN)") (class "Default")
      (node (ref "C41L") (pin "2") (pinfunction "2_2") (pintype "passive"))
      (node (ref "R41L") (pin "1") (pinfunction "1_1") (pintype "passive"))
      (node (ref "U2") (pin "5") (pinfunction "+IN_5") (pintype "input"))
    )
    (net (code "51") (name "Net-(U2B--IN)") (class "Default")
      (node (ref "R42L") (pin "1") (pinfunction "1_1") (pintype "passive"))
      (node (ref "R43L") (pin "2") (pinfunction "2_2") (pintype "passive"))
      (node (ref "U2") (pin "6") (pinfunction "-IN_6") (pintype "input"))
    )
    (net (code "52") (name "Net-(U2B-OUT)") (class "Default")
      (node (ref "RSUPP_L") (pin "2") (pinfunction "2_2") (pintype "passive"))
      (node (ref "U2") (pin "7") (pinfunction "OUT_7") (pintype "output"))
    )
    (net (code "53") (name "Net-(U3-C+)") (class "Default")
      (node (ref "C13") (pin "+") (pinfunction "+_+") (pintype "passive"))
      (node (ref "U3") (pin "2") (pinfunction "C+_2") (pintype "passive"))
    )
    (net (code "54") (name "Net-(U3-C-)") (class "Default")
      (node (ref "C13") (pin "-") (pinfunction "-_-") (pintype "passive"))
      (node (ref "U3") (pin "4") (pinfunction "C-_4") (pintype "passive"))
    )
    (net (code "55") (name "Net-(U3-FREQX2)") (class "Default")
      (node (ref "FREQX2") (pin "1") (pinfunction "1_1") (pintype "passive"))
      (node (ref "U3") (pin "6") (pinfunction "FREQX2_6") (pintype "passive"))
    )
    (net (code "56") (name "SUSPEND") (class "Default")
      (node (ref "U1") (pin "27") (pinfunction "~{SSPND}_27") (pintype "output"))
    )
    (net (code "59") (name "VBUS") (class "Default")
      (node (ref "R12") (pin "2") (pinfunction "2_2") (pintype "passive"))
      (node (ref "R13") (pin "1") (pinfunction "1_1") (pintype "passive"))
      (node (ref "R14") (pin "1") (pinfunction "1_1") (pintype "passive"))
      (node (ref "U1") (pin "21") (pinfunction "HOST_21") (pintype "input"))
      (node (ref "VBUS") (pin "TP") (pinfunction "TP_TP") (pintype "input"))
      (node (ref "X2") (pin "1") (pinfunction "1_1") (pintype "passive"))
    )
    (net (code "60") (name "unconnected-(CN2-P$3-Pad2)") (class "Default")
      (node (ref "CN2") (pin "2") (pinfunction "P$3_2") (pintype "bidirectional"))
    )
    (net (code "61") (name "unconnected-(CN2-P$4-Pad4)") (class "Default")
      (node (ref "CN2") (pin "4") (pinfunction "P$4_4") (pintype "bidirectional"))
    )
    (net (code "62") (name "unconnected-(L1-Pad1)") (class "Default")
      (node (ref "L1") (pin "1") (pinfunction "1_1") (pintype "passive"))
    )
    (net (code "63") (name "unconnected-(L1-Pad2)") (class "Default")
      (node (ref "L1") (pin "2") (pinfunction "2_2") (pintype "passive"))
    )
    (net (code "64") (name "unconnected-(MP1-D-Pad3)") (class "Default")
      (node (ref "MP1") (pin "3") (pinfunction "D_3") (pintype "passive"))
    )
    (net (code "65") (name "unconnected-(MP1-G-Pad1)") (class "Default")
      (node (ref "MP1") (pin "1") (pinfunction "G_1") (pintype "passive"))
    )
    (net (code "66") (name "unconnected-(MP1-S-Pad2)") (class "Default")
      (node (ref "MP1") (pin "2") (pinfunction "S_2") (pintype "passive"))
    )
    (net (code "67") (name "unconnected-(U3-COSC-Pad7)") (class "Default")
      (node (ref "U3") (pin "7") (pinfunction "COSC_7") (pintype "passive"))
    )
    (net (code "68") (name "unconnected-(U3-ZENER_CAT-Pad1)") (class "Default")
      (node (ref "U3") (pin "1") (pinfunction "ZENER_CAT_1") (pintype "passive"))
    )
  )
)
